# IO_Peripherals.net
KiCad netlist of a schematic drawn in Altium Designer
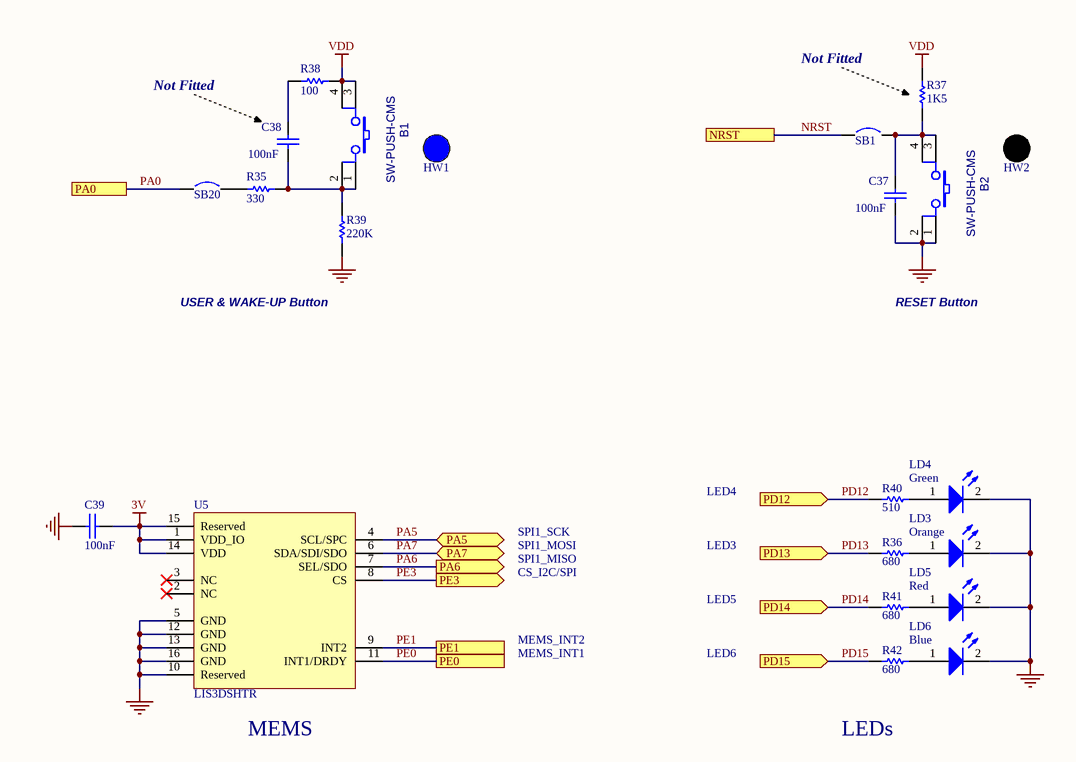
[diagram p0: IO Peripherals.SchDoc]

(export (version "E")
  (design (tool "Eeschema 10.0.6"))
  (components
    (comp (ref "B1")
      (value "SW-PUSH-CMS")
      (footprint "SW4SMD")
      (description "Non-Open Push-Button 0.1A 24V")
      (libsource (lib "MB997") (part "SW-PUSH-CMS_NEW"))
    )
    (comp (ref "B2")
      (value "SW-PUSH-CMS")
      (footprint "SW4SMD")
      (description "Non-Open Push-Button 0.1A 24V")
      (libsource (lib "MB997") (part "SW-PUSH-CMS_NEW"))
    )
    (comp (ref "C37")
      (value "100nF")
      (footprint "0402C")
      (description "Capacitor")
      (fields (field (name "PUBLISHER") "Altium Limited"))
      (libsource (lib "Miscellaneous Devices") (part "CAP"))
    )
    (comp (ref "C38")
      (value "100nF")
      (footprint "0402C")
      (description "Capacitor")
      (fields (field (name "PUBLISHER") "Altium Limited"))
      (libsource (lib "Miscellaneous Devices") (part "CAP"))
    )
    (comp (ref "C39")
      (value "100nF")
      (footprint "0402C")
      (description "Capacitor")
      (libsource (lib "*") (part "CAP"))
    )
    (comp (ref "HW1")
      (value "BUTTON_HAT_BLUE")
      (description "switch hat,blue")
      (libsource (lib "MB997") (part "BUTTON_HAT_BLUE"))
    )
    (comp (ref "HW2")
      (value "BUTTON_HAT_BLACK")
      (description "switch hat,black")
      (libsource (lib "MB997") (part "BUTTON_HAT_BLACK"))
    )
    (comp (ref "LD3")
      (value "Orange")
      (footprint "LED0603")
      (description "Typical RED, GREEN, YELLOW, AMBER GaAs LED")
      (fields (field (name "PUBLISHER") "Altium Limited"))
      (libsource (lib "Miscellaneous Devices") (part "LED2"))
    )
    (comp (ref "LD4")
      (value "Green")
      (footprint "LED0603")
      (description "Typical RED, GREEN, YELLOW, AMBER GaAs LED")
      (fields (field (name "PUBLISHER") "Altium Limited"))
      (libsource (lib "Miscellaneous Devices") (part "LED2"))
    )
    (comp (ref "LD5")
      (value "Red")
      (footprint "LED0603")
      (description "Typical RED, GREEN, YELLOW, AMBER GaAs LED")
      (fields (field (name "PUBLISHER") "Altium Limited"))
      (libsource (lib "Miscellaneous Devices") (part "LED2"))
    )
    (comp (ref "LD6")
      (value "Blue")
      (footprint "LED0603")
      (description "Typical RED, GREEN, YELLOW, AMBER GaAs LED")
      (fields (field (name "PUBLISHER") "Altium Limited"))
      (libsource (lib "Miscellaneous Devices") (part "LED2"))
    )
    (comp (ref "R35")
      (value "330")
      (description "Resistor")
      (fields (field (name "PUBLISHER") "Altium Limited"))
      (libsource (lib "Miscellaneous Devices") (part "res1"))
    )
    (comp (ref "R36")
      (value "680")
      (footprint "0603R")
      (description "Resistor")
      (fields (field (name "PUBLISHER") "Altium Limited"))
      (libsource (lib "Miscellaneous Devices") (part "Res1"))
    )
    (comp (ref "R37")
      (value "1K5")
      (footprint "0402R")
      (description "Resistor")
      (fields (field (name "PUBLISHER") "Altium Limited"))
      (libsource (lib "Miscellaneous Devices") (part "res1"))
    )
    (comp (ref "R38")
      (value "100")
      (footprint "0402R")
      (description "Resistor")
      (fields (field (name "PUBLISHER") "Altium Limited"))
      (libsource (lib "Miscellaneous Devices") (part "res1"))
    )
    (comp (ref "R39")
      (value "220K")
      (description "Resistor")
      (fields (field (name "PUBLISHER") "Altium Limited"))
      (libsource (lib "Miscellaneous Devices") (part "res1"))
    )
    (comp (ref "R40")
      (value "510")
      (footprint "0603R")
      (description "Resistor")
      (fields (field (name "PUBLISHER") "Altium Limited"))
      (libsource (lib "Miscellaneous Devices") (part "Res1"))
    )
    (comp (ref "R41")
      (value "680")
      (footprint "0603R")
      (description "Resistor")
      (fields (field (name "PUBLISHER") "Altium Limited"))
      (libsource (lib "Miscellaneous Devices") (part "Res1"))
    )
    (comp (ref "R42")
      (value "680")
      (footprint "0603R")
      (description "Resistor")
      (fields (field (name "PUBLISHER") "Altium Limited"))
      (libsource (lib "Miscellaneous Devices") (part "Res1"))
    )
    (comp (ref "SB1")
      (value "Circuit Breaker")
      (footprint "JUMPER")
      (fields (field (name "PUBLISHER") "Altium Limited"))
      (libsource (lib "MB915") (part "Circuit Breaker"))
    )
    (comp (ref "SB20")
      (value "Circuit Breaker")
      (footprint "JUMPER")
      (fields (field (name "PUBLISHER") "Altium Limited"))
      (libsource (lib "MB915") (part "Circuit Breaker"))
    )
    (comp (ref "U5")
      (value "LIS3DSHTR")
      (footprint "LGA16_")
      (description "MEMS motion sensor 3-axis - ±2g/±4g/±6g/±8g/±16g digital output accelerometer")
      (libsource (lib "MB997") (part "LIS3DSH_"))
    )
  )
  (nets
    (net (code "1") (name "/NRST") (class "Default")
      (node (ref "SB1") (pin "1") (pinfunction "1_1") (pintype "passive"))
    )
    (net (code "2") (name "/PA0") (class "Default")
      (node (ref "SB20") (pin "1") (pinfunction "1_1") (pintype "passive"))
    )
    (net (code "3") (name "/PA5") (class "Default")
      (node (ref "U5") (pin "4") (pinfunction "SCL/SPC_4") (pintype "passive"))
    )
    (net (code "4") (name "/PA6") (class "Default")
      (node (ref "U5") (pin "7") (pinfunction "SEL/SDO_7") (pintype "passive"))
    )
    (net (code "5") (name "/PA7") (class "Default")
      (node (ref "U5") (pin "6") (pinfunction "SDA/SDI/SDO_6") (pintype "passive"))
    )
    (net (code "6") (name "/PD12") (class "Default")
      (node (ref "R40") (pin "2") (pinfunction "2_2") (pintype "passive"))
    )
    (net (code "7") (name "/PD13") (class "Default")
      (node (ref "R36") (pin "2") (pinfunction "2_2") (pintype "passive"))
    )
    (net (code "8") (name "/PD14") (class "Default")
      (node (ref "R41") (pin "2") (pinfunction "2_2") (pintype "passive"))
    )
    (net (code "9") (name "/PD15") (class "Default")
      (node (ref "R42") (pin "2") (pinfunction "2_2") (pintype "passive"))
    )
    (net (code "10") (name "/PE0") (class "Default")
      (node (ref "U5") (pin "11") (pinfunction "INT1/DRDY_11") (pintype "passive"))
    )
    (net (code "11") (name "/PE1") (class "Default")
      (node (ref "U5") (pin "9") (pinfunction "INT2_9") (pintype "passive"))
    )
    (net (code "12") (name "/PE3") (class "Default")
      (node (ref "U5") (pin "8") (pinfunction "CS_8") (pintype "passive"))
    )
    (net (code "13") (name "3V") (class "Default")
      (node (ref "C39") (pin "2") (pinfunction "2_2") (pintype "passive"))
      (node (ref "U5") (pin "1") (pinfunction "VDD_IO_1") (pintype "passive"))
      (node (ref "U5") (pin "14") (pinfunction "VDD_14") (pintype "passive"))
      (node (ref "U5") (pin "15") (pinfunction "Reserved_15") (pintype "passive"))
    )
    (net (code "14") (name "GND") (class "Default")
      (node (ref "B2") (pin "1") (pinfunction "1_1") (pintype "passive"))
      (node (ref "B2") (pin "2") (pinfunction "2_2") (pintype "passive"))
      (node (ref "C37") (pin "1") (pinfunction "1_1") (pintype "passive"))
      (node (ref "C39") (pin "1") (pinfunction "1_1") (pintype "passive"))
      (node (ref "LD3") (pin "2") (pinfunction "K_2") (pintype "passive"))
      (node (ref "LD4") (pin "2") (pinfunction "K_2") (pintype "passive"))
      (node (ref "LD5") (pin "2") (pinfunction "K_2") (pintype "passive"))
      (node (ref "LD6") (pin "2") (pinfunction "K_2") (pintype "passive"))
      (node (ref "R39") (pin "1") (pinfunction "1_1") (pintype "passive"))
      (node (ref "U5") (pin "10") (pinfunction "Reserved_10") (pintype "passive"))
      (node (ref "U5") (pin "12") (pinfunction "GND_12") (pintype "passive"))
      (node (ref "U5") (pin "13") (pinfunction "GND_13") (pintype "passive"))
      (node (ref "U5") (pin "16") (pinfunction "GND_16") (pintype "passive"))
      (node (ref "U5") (pin "5") (pinfunction "GND_5") (pintype "passive"))
    )
    (net (code "15") (name "Net-(B1-Pad1)") (class "Default")
      (node (ref "B1") (pin "1") (pinfunction "1_1") (pintype "passive"))
      (node (ref "B1") (pin "2") (pinfunction "2_2") (pintype "passive"))
      (node (ref "C38") (pin "1") (pinfunction "1_1") (pintype "passive"))
      (node (ref "R35") (pin "2") (pinfunction "2_2") (pintype "passive"))
      (node (ref "R39") (pin "2") (pinfunction "2_2") (pintype "passive"))
    )
    (net (code "16") (name "Net-(B2-Pad3)") (class "Default")
      (node (ref "B2") (pin "3") (pinfunction "3_3") (pintype "passive"))
      (node (ref "B2") (pin "4") (pinfunction "4_4") (pintype "passive"))
      (node (ref "C37") (pin "2") (pinfunction "2_2") (pintype "passive"))
      (node (ref "R37") (pin "1") (pinfunction "1_1") (pintype "passive"))
      (node (ref "SB1") (pin "2") (pinfunction "2_2") (pintype "passive"))
    )
    (net (code "17") (name "Net-(C38-Pad2)") (class "Default")
      (node (ref "C38") (pin "2") (pinfunction "2_2") (pintype "passive"))
      (node (ref "R38") (pin "1") (pinfunction "1_1") (pintype "passive"))
    )
    (net (code "18") (name "Net-(LD3-A)") (class "Default")
      (node (ref "LD3") (pin "1") (pinfunction "A_1") (pintype "passive"))
      (node (ref "R36") (pin "1") (pinfunction "1_1") (pintype "passive"))
    )
    (net (code "19") (name "Net-(LD4-A)") (class "Default")
      (node (ref "LD4") (pin "1") (pinfunction "A_1") (pintype "passive"))
      (node (ref "R40") (pin "1") (pinfunction "1_1") (pintype "passive"))
    )
    (net (code "20") (name "Net-(LD5-A)") (class "Default")
      (node (ref "LD5") (pin "1") (pinfunction "A_1") (pintype "passive"))
      (node (ref "R41") (pin "1") (pinfunction "1_1") (pintype "passive"))
    )
    (net (code "21") (name "Net-(LD6-A)") (class "Default")
      (node (ref "LD6") (pin "1") (pinfunction "A_1") (pintype "passive"))
      (node (ref "R42") (pin "1") (pinfunction "1_1") (pintype "passive"))
    )
    (net (code "22") (name "Net-(R35-Pad1)") (class "Default")
      (node (ref "R35") (pin "1") (pinfunction "1_1") (pintype "passive"))
      (node (ref "SB20") (pin "2") (pinfunction "2_2") (pintype "passive"))
    )
    (net (code "23") (name "VDD") (class "Default")
      (node (ref "B1") (pin "3") (pinfunction "3_3") (pintype "passive"))
      (node (ref "B1") (pin "4") (pinfunction "4_4") (pintype "passive"))
      (node (ref "R37") (pin "2") (pinfunction "2_2") (pintype "passive"))
      (node (ref "R38") (pin "2") (pinfunction "2_2") (pintype "passive"))
    )
    (net (code "24") (name "unconnected-(U5-NC-Pad2)") (class "Default")
      (node (ref "U5") (pin "2") (pinfunction "NC_2") (pintype "passive+no_connect"))
    )
    (net (code "25") (name "unconnected-(U5-NC-Pad3)") (class "Default")
      (node (ref "U5") (pin "3") (pinfunction "NC_3") (pintype "passive+no_connect"))
    )
  )
)
